# NavigationBoard.net
KiCad netlist of a schematic drawn in EAGLE
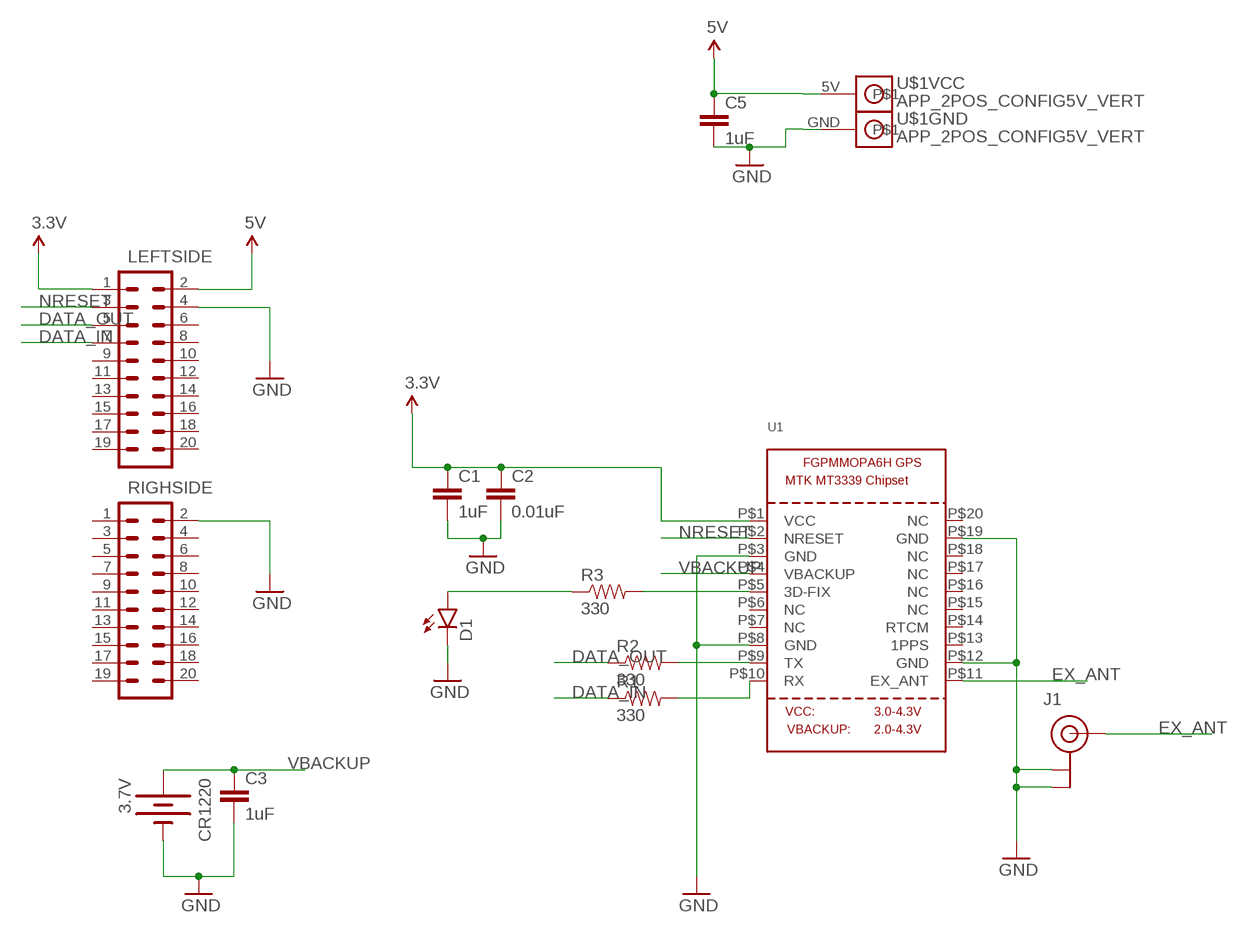
[diagram p0: schematic, sheet 1]

(export (version "E")
  (design (tool "Eeschema 10.0.6"))
  (components
    (comp (ref "C1")
      (value "1uF")
      (footprint "eagle-import:1206")
      (libsource (lib "eagle-import") (part "CAP1206"))
    )
    (comp (ref "C2")
      (value "0.01uF")
      (footprint "eagle-import:1206")
      (libsource (lib "eagle-import") (part "CAP1206"))
    )
    (comp (ref "C3")
      (value "1uF")
      (footprint "eagle-import:1206")
      (libsource (lib "eagle-import") (part "CAP1206"))
    )
    (comp (ref "C5")
      (value "1uF")
      (footprint "eagle-import:1206")
      (libsource (lib "eagle-import") (part "CAP1206"))
    )
    (comp (ref "CR1220")
      (value "3.7V")
      (footprint "eagle-import:BATTCON_12MM")
      (libsource (lib "eagle-import") (part "BATTERY12MM"))
    )
    (comp (ref "D1")
      (value "LED1206")
      (footprint "eagle-import:LED-1206")
      (libsource (lib "eagle-import") (part "LED1206"))
    )
    (comp (ref "J1")
      (value "U.FL")
      (footprint "eagle-import:U.FL")
      (libsource (lib "eagle-import") (part "U.FL"))
    )
    (comp (ref "LEFTSIDE")
      (value "M10X2")
      (footprint "eagle-import:2X10")
      (libsource (lib "eagle-import") (part "M10X2"))
    )
    (comp (ref "R1")
      (value "330")
      (footprint "eagle-import:1206")
      (libsource (lib "eagle-import") (part "RESISTOR1206"))
    )
    (comp (ref "R2")
      (value "330")
      (footprint "eagle-import:1206")
      (libsource (lib "eagle-import") (part "RESISTOR1206"))
    )
    (comp (ref "R3")
      (value "330")
      (footprint "eagle-import:1206")
      (libsource (lib "eagle-import") (part "RESISTOR1206"))
    )
    (comp (ref "RIGHSIDE")
      (value "M10X2")
      (footprint "eagle-import:2X10")
      (libsource (lib "eagle-import") (part "M10X2"))
    )
    (comp (ref "U$1")
      (value "APP_2POS_CONFIG5V_VERT")
      (footprint "eagle-import:APP45_5V_VERT_CONFIG")
      (libsource (lib "eagle-import") (part "APP_2POS_CONFIG5V_VERT"))
    )
    (comp (ref "U1")
      (value "GPS_FGPMMOPA6H")
      (footprint "eagle-import:FGPMMOPA6H")
      (libsource (lib "eagle-import") (part "GPS_FGPMMOPA6H"))
    )
  )
  (nets
    (net (code "1") (name "/DATA_IN") (class "Default")
      (node (ref "LEFTSIDE") (pin "7") (pinfunction "7_7") (pintype "passive"))
      (node (ref "R1") (pin "1") (pinfunction "1_1") (pintype "passive"))
    )
    (net (code "2") (name "/DATA_OUT") (class "Default")
      (node (ref "LEFTSIDE") (pin "5") (pinfunction "5_5") (pintype "passive"))
      (node (ref "R2") (pin "1") (pinfunction "1_1") (pintype "passive"))
    )
    (net (code "3") (name "/EX_ANT") (class "Default")
      (node (ref "J1") (pin "P$3") (pinfunction "SIGNAL_P$3") (pintype "bidirectional"))
      (node (ref "U1") (pin "P$11") (pinfunction "EX_ANT_P$11") (pintype "bidirectional"))
    )
    (net (code "4") (name "/NRESET") (class "Default")
      (node (ref "LEFTSIDE") (pin "3") (pinfunction "3_3") (pintype "passive"))
      (node (ref "U1") (pin "P$2") (pinfunction "NRESET_P$2") (pintype "bidirectional"))
    )
    (net (code "5") (name "/VBACKUP") (class "Default")
      (node (ref "C3") (pin "1") (pinfunction "1_1") (pintype "passive"))
      (node (ref "CR1220") (pin "PWR@1") (pinfunction "+_PWR@1") (pintype "power_in"))
      (node (ref "U1") (pin "P$4") (pinfunction "VBACKUP_P$4") (pintype "bidirectional"))
    )
    (net (code "6") (name "3.3V") (class "Default")
      (node (ref "C1") (pin "1") (pinfunction "1_1") (pintype "passive"))
      (node (ref "C2") (pin "1") (pinfunction "1_1") (pintype "passive"))
      (node (ref "LEFTSIDE") (pin "1") (pinfunction "1_1") (pintype "passive"))
      (node (ref "U1") (pin "P$1") (pinfunction "VCC_P$1") (pintype "bidirectional"))
    )
    (net (code "7") (name "5V") (class "Default")
      (node (ref "C5") (pin "1") (pinfunction "1_1") (pintype "passive"))
      (node (ref "LEFTSIDE") (pin "2") (pinfunction "2_2") (pintype "passive"))
      (node (ref "U$1") (pin "5V") (pinfunction "P$1_5V") (pintype "bidirectional"))
    )
    (net (code "8") (name "GND") (class "Default")
      (node (ref "C1") (pin "2") (pinfunction "2_2") (pintype "passive"))
      (node (ref "C2") (pin "2") (pinfunction "2_2") (pintype "passive"))
      (node (ref "C3") (pin "2") (pinfunction "2_2") (pintype "passive"))
      (node (ref "C5") (pin "2") (pinfunction "2_2") (pintype "passive"))
      (node (ref "CR1220") (pin "GND") (pinfunction "-_GND") (pintype "power_in"))
      (node (ref "D1") (pin "C") (pinfunction "C_C") (pintype "passive"))
      (node (ref "J1") (pin "P$1") (pinfunction "GND_P$1") (pintype "bidirectional"))
      (node (ref "J1") (pin "P$2") (pinfunction "GND_P$2") (pintype "bidirectional"))
      (node (ref "LEFTSIDE") (pin "4") (pinfunction "4_4") (pintype "passive"))
      (node (ref "RIGHSIDE") (pin "2") (pinfunction "2_2") (pintype "passive"))
      (node (ref "U$1") (pin "GND") (pinfunction "P$1_GND") (pintype "bidirectional"))
      (node (ref "U1") (pin "P$12") (pinfunction "GND_P$12") (pintype "bidirectional"))
      (node (ref "U1") (pin "P$19") (pinfunction "GND_P$19") (pintype "bidirectional"))
      (node (ref "U1") (pin "P$3") (pinfunction "GND_P$3") (pintype "bidirectional"))
      (node (ref "U1") (pin "P$8") (pinfunction "GND_P$8") (pintype "bidirectional"))
    )
    (net (code "9") (name "Net-(D1-PadA)") (class "Default")
      (node (ref "D1") (pin "A") (pinfunction "A_A") (pintype "passive"))
      (node (ref "R3") (pin "1") (pinfunction "1_1") (pintype "passive"))
    )
    (net (code "10") (name "Net-(U1-3D-FIX)") (class "Default")
      (node (ref "R3") (pin "2") (pinfunction "2_2") (pintype "passive"))
      (node (ref "U1") (pin "P$5") (pinfunction "3D-FIX_P$5") (pintype "bidirectional"))
    )
    (net (code "11") (name "Net-(U1-RX)") (class "Default")
      (node (ref "R1") (pin "2") (pinfunction "2_2") (pintype "passive"))
      (node (ref "U1") (pin "P$10") (pinfunction "RX_P$10") (pintype "bidirectional"))
    )
    (net (code "12") (name "Net-(U1-TX)") (class "Default")
      (node (ref "R2") (pin "2") (pinfunction "2_2") (pintype "passive"))
      (node (ref "U1") (pin "P$9") (pinfunction "TX_P$9") (pintype "bidirectional"))
    )
    (net (code "13") (name "unconnected-(LEFTSIDE-Pad6)") (class "Default")
      (node (ref "LEFTSIDE") (pin "6") (pinfunction "6_6") (pintype "passive"))
    )
    (net (code "14") (name "unconnected-(LEFTSIDE-Pad8)") (class "Default")
      (node (ref "LEFTSIDE") (pin "8") (pinfunction "8_8") (pintype "passive"))
    )
    (net (code "15") (name "unconnected-(LEFTSIDE-Pad9)") (class "Default")
      (node (ref "LEFTSIDE") (pin "9") (pinfunction "9_9") (pintype "passive"))
    )
    (net (code "16") (name "unconnected-(LEFTSIDE-Pad10)") (class "Default")
      (node (ref "LEFTSIDE") (pin "10") (pinfunction "10_10") (pintype "passive"))
    )
    (net (code "17") (name "unconnected-(LEFTSIDE-Pad11)") (class "Default")
      (node (ref "LEFTSIDE") (pin "11") (pinfunction "11_11") (pintype "passive"))
    )
    (net (code "18") (name "unconnected-(LEFTSIDE-Pad12)") (class "Default")
      (node (ref "LEFTSIDE") (pin "12") (pinfunction "12_12") (pintype "passive"))
    )
    (net (code "19") (name "unconnected-(LEFTSIDE-Pad13)") (class "Default")
      (node (ref "LEFTSIDE") (pin "13") (pinfunction "13_13") (pintype "passive"))
    )
    (net (code "20") (name "unconnected-(LEFTSIDE-Pad14)") (class "Default")
      (node (ref "LEFTSIDE") (pin "14") (pinfunction "14_14") (pintype "passive"))
    )
    (net (code "21") (name "unconnected-(LEFTSIDE-Pad15)") (class "Default")
      (node (ref "LEFTSIDE") (pin "15") (pinfunction "15_15") (pintype "passive"))
    )
    (net (code "22") (name "unconnected-(LEFTSIDE-Pad16)") (class "Default")
      (node (ref "LEFTSIDE") (pin "16") (pinfunction "16_16") (pintype "passive"))
    )
    (net (code "23") (name "unconnected-(LEFTSIDE-Pad17)") (class "Default")
      (node (ref "LEFTSIDE") (pin "17") (pinfunction "17_17") (pintype "passive"))
    )
    (net (code "24") (name "unconnected-(LEFTSIDE-Pad18)") (class "Default")
      (node (ref "LEFTSIDE") (pin "18") (pinfunction "18_18") (pintype "passive"))
    )
    (net (code "25") (name "unconnected-(LEFTSIDE-Pad19)") (class "Default")
      (node (ref "LEFTSIDE") (pin "19") (pinfunction "19_19") (pintype "passive"))
    )
    (net (code "26") (name "unconnected-(LEFTSIDE-Pad20)") (class "Default")
      (node (ref "LEFTSIDE") (pin "20") (pinfunction "20_20") (pintype "passive"))
    )
    (net (code "27") (name "unconnected-(RIGHSIDE-Pad1)") (class "Default")
      (node (ref "RIGHSIDE") (pin "1") (pinfunction "1_1") (pintype "passive"))
    )
    (net (code "28") (name "unconnected-(RIGHSIDE-Pad3)") (class "Default")
      (node (ref "RIGHSIDE") (pin "3") (pinfunction "3_3") (pintype "passive"))
    )
    (net (code "29") (name "unconnected-(RIGHSIDE-Pad4)") (class "Default")
      (node (ref "RIGHSIDE") (pin "4") (pinfunction "4_4") (pintype "passive"))
    )
    (net (code "30") (name "unconnected-(RIGHSIDE-Pad5)") (class "Default")
      (node (ref "RIGHSIDE") (pin "5") (pinfunction "5_5") (pintype "passive"))
    )
    (net (code "31") (name "unconnected-(RIGHSIDE-Pad6)") (class "Default")
      (node (ref "RIGHSIDE") (pin "6") (pinfunction "6_6") (pintype "passive"))
    )
    (net (code "32") (name "unconnected-(RIGHSIDE-Pad7)") (class "Default")
      (node (ref "RIGHSIDE") (pin "7") (pinfunction "7_7") (pintype "passive"))
    )
    (net (code "33") (name "unconnected-(RIGHSIDE-Pad8)") (class "Default")
      (node (ref "RIGHSIDE") (pin "8") (pinfunction "8_8") (pintype "passive"))
    )
    (net (code "34") (name "unconnected-(RIGHSIDE-Pad9)") (class "Default")
      (node (ref "RIGHSIDE") (pin "9") (pinfunction "9_9") (pintype "passive"))
    )
    (net (code "35") (name "unconnected-(RIGHSIDE-Pad10)") (class "Default")
      (node (ref "RIGHSIDE") (pin "10") (pinfunction "10_10") (pintype "passive"))
    )
    (net (code "36") (name "unconnected-(RIGHSIDE-Pad11)") (class "Default")
      (node (ref "RIGHSIDE") (pin "11") (pinfunction "11_11") (pintype "passive"))
    )
    (net (code "37") (name "unconnected-(RIGHSIDE-Pad12)") (class "Default")
      (node (ref "RIGHSIDE") (pin "12") (pinfunction "12_12") (pintype "passive"))
    )
    (net (code "38") (name "unconnected-(RIGHSIDE-Pad13)") (class "Default")
      (node (ref "RIGHSIDE") (pin "13") (pinfunction "13_13") (pintype "passive"))
    )
    (net (code "39") (name "unconnected-(RIGHSIDE-Pad14)") (class "Default")
      (node (ref "RIGHSIDE") (pin "14") (pinfunction "14_14") (pintype "passive"))
    )
    (net (code "40") (name "unconnected-(RIGHSIDE-Pad15)") (class "Default")
      (node (ref "RIGHSIDE") (pin "15") (pinfunction "15_15") (pintype "passive"))
    )
    (net (code "41") (name "unconnected-(RIGHSIDE-Pad16)") (class "Default")
      (node (ref "RIGHSIDE") (pin "16") (pinfunction "16_16") (pintype "passive"))
    )
    (net (code "42") (name "unconnected-(RIGHSIDE-Pad17)") (class "Default")
      (node (ref "RIGHSIDE") (pin "17") (pinfunction "17_17") (pintype "passive"))
    )
    (net (code "43") (name "unconnected-(RIGHSIDE-Pad18)") (class "Default")
      (node (ref "RIGHSIDE") (pin "18") (pinfunction "18_18") (pintype "passive"))
    )
    (net (code "44") (name "unconnected-(RIGHSIDE-Pad19)") (class "Default")
      (node (ref "RIGHSIDE") (pin "19") (pinfunction "19_19") (pintype "passive"))
    )
    (net (code "45") (name "unconnected-(RIGHSIDE-Pad20)") (class "Default")
      (node (ref "RIGHSIDE") (pin "20") (pinfunction "20_20") (pintype "passive"))
    )
    (net (code "46") (name "unconnected-(U1-1PPS-PadP$13)") (class "Default")
      (node (ref "U1") (pin "P$13") (pinfunction "1PPS_P$13") (pintype "bidirectional"))
    )
    (net (code "47") (name "unconnected-(U1-NC-PadP$6)") (class "Default")
      (node (ref "U1") (pin "P$6") (pinfunction "NC_P$6") (pintype "bidirectional"))
    )
    (net (code "48") (name "unconnected-(U1-NC-PadP$7)") (class "Default")
      (node (ref "U1") (pin "P$7") (pinfunction "NC_P$7") (pintype "bidirectional"))
    )
    (net (code "49") (name "unconnected-(U1-NC-PadP$15)") (class "Default")
      (node (ref "U1") (pin "P$15") (pinfunction "NC_P$15") (pintype "bidirectional"))
    )
    (net (code "50") (name "unconnected-(U1-NC-PadP$16)") (class "Default")
      (node (ref "U1") (pin "P$16") (pinfunction "NC_P$16") (pintype "bidirectional"))
    )
    (net (code "51") (name "unconnected-(U1-NC-PadP$17)") (class "Default")
      (node (ref "U1") (pin "P$17") (pinfunction "NC_P$17") (pintype "bidirectional"))
    )
    (net (code "52") (name "unconnected-(U1-NC-PadP$18)") (class "Default")
      (node (ref "U1") (pin "P$18") (pinfunction "NC_P$18") (pintype "bidirectional"))
    )
    (net (code "53") (name "unconnected-(U1-NC-PadP$20)") (class "Default")
      (node (ref "U1") (pin "P$20") (pinfunction "NC_P$20") (pintype "bidirectional"))
    )
    (net (code "54") (name "unconnected-(U1-RTCM-PadP$14)") (class "Default")
      (node (ref "U1") (pin "P$14") (pinfunction "RTCM_P$14") (pintype "bidirectional"))
    )
  )
)
